# T4F81_FPGA.net
KiCad netlist of a schematic drawn in Altium Designer
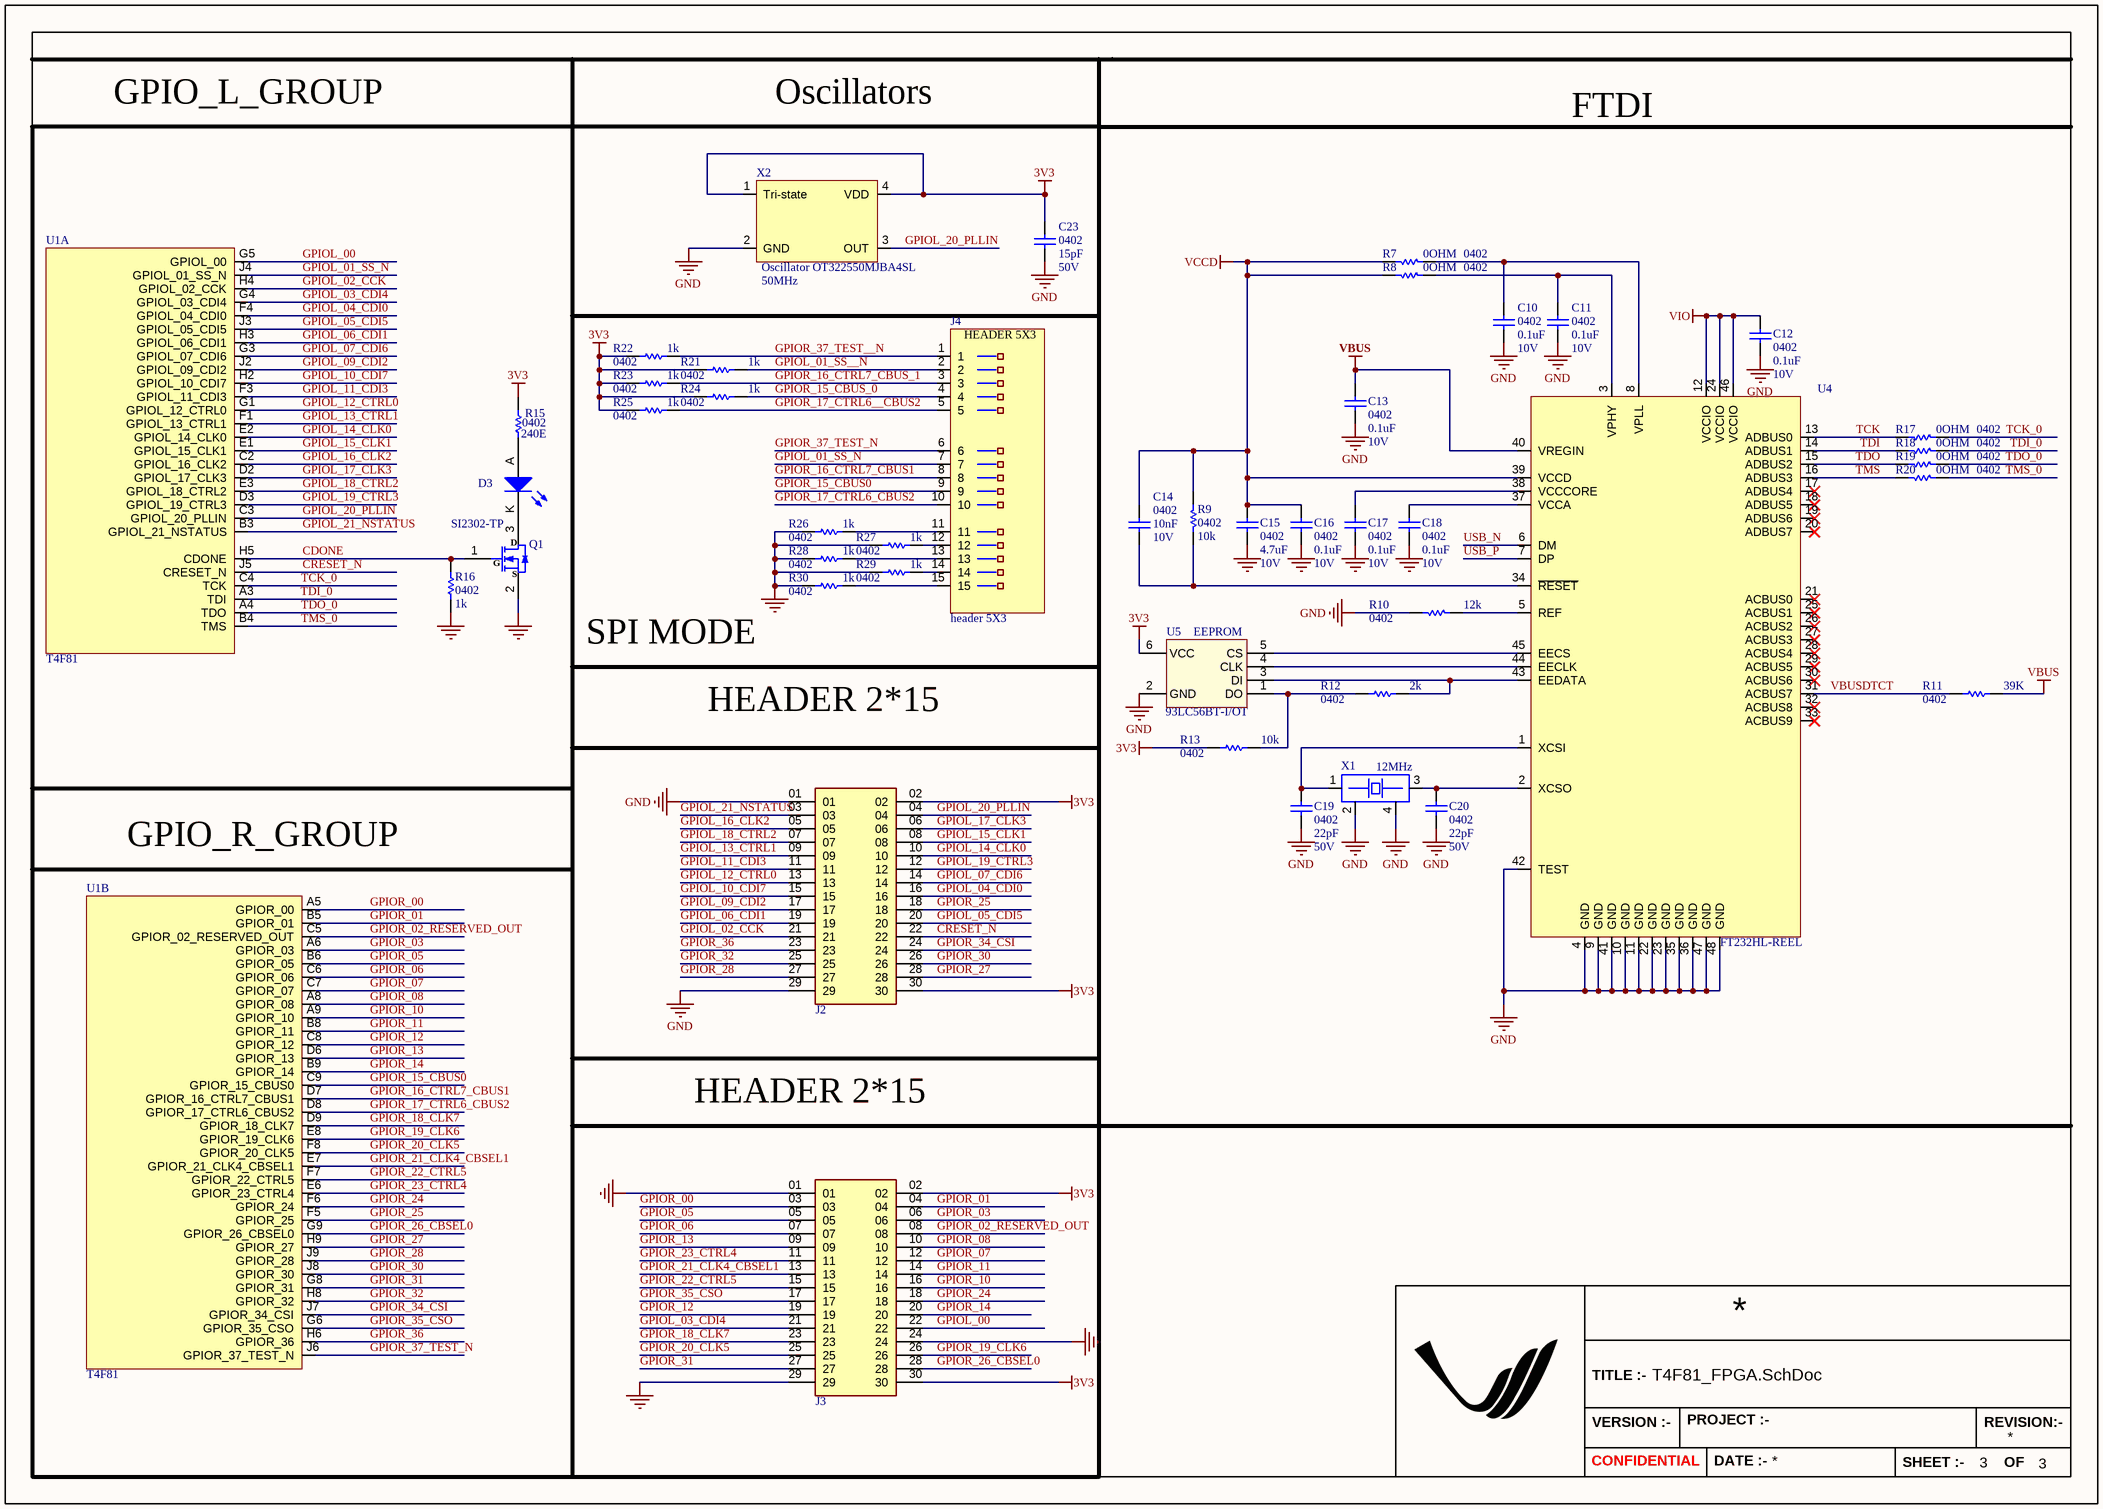
[diagram p0: T4F81_FPGA.SchDoc]

(export (version "E")
  (design (tool "Eeschema 10.0.6"))
  (components
    (comp (ref "C10")
      (value "0.1uF")
      (footprint "CAPC0402")
      (description "Ceramic Capacitor, 0.1uF, 0402,10V")
      (fields (field (name "CASE/PACKAGE") "0402") (field (name "VOLTAGE") "10V"))
      (libsource (lib "Pd's Sch Lib") (part "Capacitor"))
    )
    (comp (ref "C11")
      (value "0.1uF")
      (footprint "CAPC0402")
      (description "Ceramic Capacitor, 0.1uF, 0402,10V")
      (fields (field (name "CASE/PACKAGE") "0402") (field (name "VOLTAGE") "10V"))
      (libsource (lib "Pd's Sch Lib") (part "Capacitor"))
    )
    (comp (ref "C12")
      (value "0.1uF")
      (footprint "CAPC0402")
      (description "Ceramic Capacitor, 0.1uF, 0402,10V")
      (fields (field (name "CASE/PACKAGE") "0402") (field (name "VOLTAGE") "10V"))
      (libsource (lib "Pd's Sch Lib") (part "Capacitor"))
    )
    (comp (ref "C13")
      (value "0.1uF")
      (footprint "CAPC0402")
      (description "Ceramic Capacitor, 0.1uF, 0402,10V")
      (fields (field (name "CASE/PACKAGE") "0402") (field (name "VOLTAGE") "10V"))
      (libsource (lib "Pd's Sch Lib") (part "Capacitor"))
    )
    (comp (ref "C14")
      (value "10nF")
      (footprint "CAPC0402")
      (description "Ceramic Capacitor, 10nF, 0402,10V")
      (fields (field (name "CASE/PACKAGE") "0402") (field (name "VOLTAGE") "10V"))
      (libsource (lib "Pd's Sch Lib") (part "Capacitor"))
    )
    (comp (ref "C15")
      (value "4.7uF")
      (footprint "CAPC0402")
      (description "Ceramic Capacitor, 4.7uF, 0402,10V")
      (fields (field (name "CASE/PACKAGE") "0402") (field (name "VOLTAGE") "10V"))
      (libsource (lib "Pd's Sch Lib") (part "Capacitor"))
    )
    (comp (ref "C16")
      (value "0.1uF")
      (footprint "CAPC0402")
      (description "Ceramic Capacitor, 0.1UF, 0402,10V")
      (fields (field (name "CASE/PACKAGE") "0402") (field (name "VOLTAGE") "10V"))
      (libsource (lib "Pd's Sch Lib") (part "Capacitor"))
    )
    (comp (ref "C17")
      (value "0.1uF")
      (footprint "CAPC0402")
      (description "Ceramic Capacitor, 0.1UF, 0402,10V")
      (fields (field (name "CASE/PACKAGE") "0402") (field (name "VOLTAGE") "10V"))
      (libsource (lib "Pd's Sch Lib") (part "Capacitor"))
    )
    (comp (ref "C18")
      (value "0.1uF")
      (footprint "CAPC0402")
      (description "Ceramic Capacitor, 0.1UF, 0402,10V")
      (fields (field (name "CASE/PACKAGE") "0402") (field (name "VOLTAGE") "10V"))
      (libsource (lib "Pd's Sch Lib") (part "Capacitor"))
    )
    (comp (ref "C19")
      (value "22pF")
      (footprint "CAPC0402")
      (description "Ceramic Capacitor, 22pF, 0402,50V")
      (fields (field (name "CASE/PACKAGE") "0402") (field (name "VOLTAGE") "50V"))
      (libsource (lib "Pd's Sch Lib") (part "Capacitor"))
    )
    (comp (ref "C20")
      (value "22pF")
      (footprint "CAPC0402")
      (description "Ceramic Capacitor, 22pF, 0402,50V")
      (fields (field (name "CASE/PACKAGE") "0402") (field (name "VOLTAGE") "50V"))
      (libsource (lib "Pd's Sch Lib") (part "Capacitor"))
    )
    (comp (ref "C23")
      (value "15pF")
      (footprint "CAPC0402")
      (description "Ceramic Capacitor, 15pF, 0402,50V")
      (fields (field (name "CASE/PACKAGE") "0402") (field (name "VOLTAGE") "50V"))
      (libsource (lib "Pd's Sch Lib") (part "Capacitor"))
    )
    (comp (ref "D3")
      (value "~")
      (footprint "led_0603")
      (description "GREEN LED, 0603")
      (fields (field (name "MANUFACTURER PART NUMBER") "GREEN"))
      (libsource (lib "CUSTOM TNY290PG") (part "LED1"))
    )
    (comp (ref "J2")
      (value "Header 15X2 2.54mm")
      (footprint "Header_15X2_2.54")
      (description "Connector Header position")
      (fields (field (name "MANUFACTURER PART NUMBER") "Th P2.54MM"))
      (libsource (lib "CUSTOM SCH") (part "Header 15X2 2.54mm"))
    )
    (comp (ref "J3")
      (value "Header 15X2 2.54mm")
      (footprint "Header_15X2_2.54")
      (description "Connector Header position")
      (fields (field (name "MANUFACTURER PART NUMBER") "Th P2.54MM"))
      (libsource (lib "CUSTOM SCH") (part "Header 15X2 2.54mm"))
    )
    (comp (ref "J4")
      (value "header 5X3")
      (footprint "HEADER_5X3_2.54 - duplicate")
      (description "HEADER 5X3 2.54MM")
      (libsource (lib "CUSTOM SCH") (part "header 5X3"))
    )
    (comp (ref "Q1")
      (value "~")
      (footprint "SOT23-3")
      (description "N-Channel 20V 3A 1.25W (Ta) Surface Mount SOT-23")
      (fields (field (name "MANUFACTURER PART NUMBER") "SI2302-TP"))
      (libsource (lib "SchLib_SPEEDSTER7T_AC7T1500") (part "MOSFET Si2302CDS"))
    )
    (comp (ref "R7")
      (value "0OHM")
      (footprint "resc0402")
      (description "Thick Film Resistor -  0ohm, 1%, 0402")
      (fields
        (field (name "MANUFACTURER PART NUMBER") "RC0402FR-070RL")
        (field (name "CASE/PACKAGE") "0402")
        (field (name "Comment") "Res1")
      )
      (libsource (lib "Miscellaneous Devices") (part "Res1"))
    )
    (comp (ref "R8")
      (value "0OHM")
      (footprint "resc0402")
      (description "Thick Film Resistor -  0ohm, 1%, 0402")
      (fields (field (name "CASE/PACKAGE") "0402") (field (name "Comment") "Res1"))
      (libsource (lib "Miscellaneous Devices") (part "Res1"))
    )
    (comp (ref "R9")
      (value "10k")
      (footprint "RESC0402")
      (description "Thick Film Resistor -  10Kohm, 1%, 0402")
      (fields (field (name "CASE/PACKAGE") "0402") (field (name "Comment") "Res1"))
      (libsource (lib "Miscellaneous Devices") (part "Res1"))
    )
    (comp (ref "R10")
      (value "12k")
      (footprint "resc0402")
      (description "Thick Film Resistor -  12Kohm, 1%, 0402")
      (fields (field (name "CASE/PACKAGE") "0402") (field (name "Comment") "Res1"))
      (libsource (lib "Miscellaneous Devices") (part "Res1"))
    )
    (comp (ref "R11")
      (value "39K")
      (footprint "CAPC0402")
      (description "Thick Film Resistor -  39Kohm, 1%, 0402")
      (fields (field (name "CASE/PACKAGE") "0402") (field (name "Comment") "Res1"))
      (libsource (lib "Miscellaneous Devices") (part "Res1"))
    )
    (comp (ref "R12")
      (value "2k")
      (footprint "resc0402")
      (description "Thick Film Resistor -  2Kohm, 1%, 0402")
      (fields (field (name "CASE/PACKAGE") "0402") (field (name "Comment") "Res1"))
      (libsource (lib "Miscellaneous Devices") (part "Res1"))
    )
    (comp (ref "R13")
      (value "10k")
      (footprint "resc0402")
      (description "Thick Film Resistor -  10Kohm, 1%, 0402")
      (fields (field (name "CASE/PACKAGE") "0402") (field (name "Comment") "Res1"))
      (libsource (lib "Miscellaneous Devices") (part "Res1"))
    )
    (comp (ref "R15")
      (value "240E")
      (footprint "RESC0402")
      (description "Thick Film Resistor -  240ohm, 1%, 0402")
      (fields (field (name "CASE/PACKAGE") "0402"))
      (libsource (lib "CUSTOM TNY290PG") (part "Res"))
    )
    (comp (ref "R16")
      (value "1k")
      (footprint "RESC0402")
      (description "Thick Film Resistor -  1Kohm, 1%, 0402")
      (fields (field (name "CASE/PACKAGE") "0402"))
      (libsource (lib "CUSTOM TNY290PG") (part "Res"))
    )
    (comp (ref "R17")
      (value "0OHM")
      (footprint "resc0402")
      (description "Thick Film Resistor -  0ohm, 1%, 0402")
      (fields
        (field (name "MANUFACTURER PART NUMBER") "RC0402FR-070RL")
        (field (name "CASE/PACKAGE") "0402")
        (field (name "Comment") "Res1")
      )
      (libsource (lib "Miscellaneous Devices") (part "Res1"))
    )
    (comp (ref "R18")
      (value "0OHM")
      (footprint "resc0402")
      (description "Thick Film Resistor -  0ohm, 1%, 0402")
      (fields
        (field (name "MANUFACTURER PART NUMBER") "RC0402FR-070RL")
        (field (name "CASE/PACKAGE") "0402")
        (field (name "Comment") "Res1")
      )
      (libsource (lib "Miscellaneous Devices") (part "Res1"))
    )
    (comp (ref "R19")
      (value "0OHM")
      (footprint "resc0402")
      (description "Thick Film Resistor -  0ohm, 1%, 0402")
      (fields
        (field (name "MANUFACTURER PART NUMBER") "RC0402FR-070RL")
        (field (name "CASE/PACKAGE") "0402")
        (field (name "Comment") "Res1")
      )
      (libsource (lib "Miscellaneous Devices") (part "Res1"))
    )
    (comp (ref "R20")
      (value "0OHM")
      (footprint "resc0402")
      (description "Thick Film Resistor -  0ohm, 1%, 0402")
      (fields
        (field (name "MANUFACTURER PART NUMBER") "RC0402FR-070RL")
        (field (name "CASE/PACKAGE") "0402")
        (field (name "Comment") "Res1")
      )
      (libsource (lib "Miscellaneous Devices") (part "Res1"))
    )
    (comp (ref "R21")
      (value "1k")
      (footprint "resc0402")
      (description "Thick Film Resistor -  1Kohm, 1%, 0402")
      (fields (field (name "CASE/PACKAGE") "0402") (field (name "Comment") "Res1"))
      (libsource (lib "Miscellaneous Devices") (part "Res1"))
    )
    (comp (ref "R22")
      (value "1k")
      (footprint "resc0402")
      (description "Thick Film Resistor -  1Kohm, 1%, 0402")
      (fields (field (name "CASE/PACKAGE") "0402") (field (name "Comment") "Res1"))
      (libsource (lib "Miscellaneous Devices") (part "Res1"))
    )
    (comp (ref "R23")
      (value "1k")
      (footprint "resc0402")
      (description "Thick Film Resistor -  1Kohm, 1%, 0402")
      (fields (field (name "CASE/PACKAGE") "0402") (field (name "Comment") "Res1"))
      (libsource (lib "Miscellaneous Devices") (part "Res1"))
    )
    (comp (ref "R24")
      (value "1k")
      (footprint "resc0402")
      (description "Thick Film Resistor -  1Kohm, 1%, 0402")
      (fields (field (name "CASE/PACKAGE") "0402") (field (name "Comment") "Res1"))
      (libsource (lib "Miscellaneous Devices") (part "Res1"))
    )
    (comp (ref "R25")
      (value "1k")
      (footprint "resc0402")
      (description "Thick Film Resistor -  1Kohm, 1%, 0402")
      (fields (field (name "CASE/PACKAGE") "0402") (field (name "Comment") "Res1"))
      (libsource (lib "Miscellaneous Devices") (part "Res1"))
    )
    (comp (ref "R26")
      (value "1k")
      (footprint "resc0402")
      (description "Thick Film Resistor -  1Kohm, 1%, 0402")
      (fields (field (name "CASE/PACKAGE") "0402") (field (name "Comment") "Res1"))
      (libsource (lib "Miscellaneous Devices") (part "Res1"))
    )
    (comp (ref "R27")
      (value "1k")
      (footprint "resc0402")
      (description "Thick Film Resistor -  1Kohm, 1%, 0402")
      (fields (field (name "CASE/PACKAGE") "0402") (field (name "Comment") "Res1"))
      (libsource (lib "Miscellaneous Devices") (part "Res1"))
    )
    (comp (ref "R28")
      (value "1k")
      (footprint "resc0402")
      (description "Thick Film Resistor -  1Kohm, 1%, 0402")
      (fields (field (name "CASE/PACKAGE") "0402") (field (name "Comment") "Res1"))
      (libsource (lib "Miscellaneous Devices") (part "Res1"))
    )
    (comp (ref "R29")
      (value "1k")
      (footprint "resc0402")
      (description "Thick Film Resistor -  1Kohm, 1%, 0402")
      (fields (field (name "CASE/PACKAGE") "0402") (field (name "Comment") "Res1"))
      (libsource (lib "Miscellaneous Devices") (part "Res1"))
    )
    (comp (ref "R30")
      (value "1k")
      (footprint "resc0402")
      (description "Thick Film Resistor -  1Kohm, 1%, 0402")
      (fields (field (name "CASE/PACKAGE") "0402") (field (name "Comment") "Res1"))
      (libsource (lib "Miscellaneous Devices") (part "Res1"))
    )
    (comp (ref "U1") (value "T4F81") (footprint "T4F81 fpga") (libsource (lib "CUSTOM SCH") (part "T4F81")))
    (comp (ref "U4")
      (value "FTDI")
      (footprint "LQFP-48")
      (fields (field (name "MANUFACTURER PART NUMBER") "FT232HL-REEL"))
      (libsource (lib "Pd's Sch Lib") (part "FT232HL"))
    )
    (comp (ref "U5")
      (value "93LC56BT-I/OT")
      (footprint "SOT23-6")
      (description "MICROCHIP - 93LC56BT-I/OT. - 2K, 128 X 16, SERIAL EE, IND ROHS COMPLIANT: YES")
      (fields (field (name "TYPE") "EEPROM") (field (name "MANUFACTURER PART NUMBER") "93LC56BT-I/OT"))
      (libsource (lib "CUSTOM TNY290PG") (part "93LC56BT-I/OT"))
    )
    (comp (ref "X1")
      (value "XC2426TR-ND")
      (footprint "Crystal_3225")
      (description "CRYSTAL 12.0000MHZ 10PF SMD")
      (fields
        (field (name "MANUFACTURER PART NUMBER") "ECS-120-10-33B-CKM-TR")
        (field (name "FREQUENCY") "12MHz")
      )
      (libsource (lib "Pd's Sch Lib") (part "CRYSTAL_1_1"))
    )
    (comp (ref "X2")
      (value "Oscillator OT322550MJBA4SL")
      (footprint "Crystal_3225")
      (description "1.8V~3.3V -40℃~+85℃ ±10ppm 50MHz SMD3225-4P Oscillators ROHS (OT322550MJBA4SL) (C717684)")
      (fields (field (name "MANUFACTURER PART NUMBER") "OT322550MJBA4SL") (field (name "FREQUENCY") "50MHz"))
      (libsource (lib "CUSTOM SCH") (part "Oscillator OT322550MJBA4SL"))
    )
  )
  (nets
    (net (code "1") (name "/CDONE") (class "Default")
      (node (ref "Q1") (pin "1") (pinfunction "G_1") (pintype "passive"))
      (node (ref "R16") (pin "1") (pinfunction "1_1") (pintype "passive"))
      (node (ref "U1") (pin "H5") (pinfunction "CDONE_H5") (pintype "passive"))
    )
    (net (code "2") (name "/CRESET_N") (class "Default")
      (node (ref "J2") (pin "22") (pinfunction "22_22") (pintype "passive"))
      (node (ref "U1") (pin "J5") (pinfunction "CRESET_N_J5") (pintype "passive"))
    )
    (net (code "3") (name "/GPIOL_00") (class "Default")
      (node (ref "J3") (pin "22") (pinfunction "22_22") (pintype "passive"))
      (node (ref "U1") (pin "G5") (pinfunction "GPIOL_00_G5") (pintype "passive"))
    )
    (net (code "4") (name "/GPIOL_01_SS_N") (class "Default")
      (node (ref "J4") (pin "7") (pinfunction "7_7") (pintype "passive"))
      (node (ref "U1") (pin "J4") (pinfunction "GPIOL_01_SS_N_J4") (pintype "passive"))
    )
    (net (code "5") (name "/GPIOL_01_SS__N") (class "Default")
      (node (ref "J4") (pin "2") (pinfunction "2_2") (pintype "passive"))
      (node (ref "R21") (pin "1") (pinfunction "1_1") (pintype "passive"))
    )
    (net (code "6") (name "/GPIOL_02_CCK") (class "Default")
      (node (ref "J2") (pin "21") (pinfunction "21_21") (pintype "passive"))
      (node (ref "U1") (pin "H4") (pinfunction "GPIOL_02_CCK_H4") (pintype "passive"))
    )
    (net (code "7") (name "/GPIOL_03_CDI4") (class "Default")
      (node (ref "J3") (pin "21") (pinfunction "21_21") (pintype "passive"))
      (node (ref "U1") (pin "G4") (pinfunction "GPIOL_03_CDI4_G4") (pintype "passive"))
    )
    (net (code "8") (name "/GPIOL_04_CDI0") (class "Default")
      (node (ref "J2") (pin "16") (pinfunction "16_16") (pintype "passive"))
      (node (ref "U1") (pin "F4") (pinfunction "GPIOL_04_CDI0_F4") (pintype "passive"))
    )
    (net (code "9") (name "/GPIOL_05_CDI5") (class "Default")
      (node (ref "J2") (pin "20") (pinfunction "20_20") (pintype "passive"))
      (node (ref "U1") (pin "J3") (pinfunction "GPIOL_05_CDI5_J3") (pintype "passive"))
    )
    (net (code "10") (name "/GPIOL_06_CDI1") (class "Default")
      (node (ref "J2") (pin "19") (pinfunction "19_19") (pintype "passive"))
      (node (ref "U1") (pin "H3") (pinfunction "GPIOL_06_CDI1_H3") (pintype "passive"))
    )
    (net (code "11") (name "/GPIOL_07_CDI6") (class "Default")
      (node (ref "J2") (pin "14") (pinfunction "14_14") (pintype "passive"))
      (node (ref "U1") (pin "G3") (pinfunction "GPIOL_07_CDI6_G3") (pintype "passive"))
    )
    (net (code "12") (name "/GPIOL_09_CDI2") (class "Default")
      (node (ref "J2") (pin "17") (pinfunction "17_17") (pintype "passive"))
      (node (ref "U1") (pin "J2") (pinfunction "GPIOL_09_CDI2_J2") (pintype "passive"))
    )
    (net (code "13") (name "/GPIOL_10_CDI7") (class "Default")
      (node (ref "J2") (pin "15") (pinfunction "15_15") (pintype "passive"))
      (node (ref "U1") (pin "H2") (pinfunction "GPIOL_10_CDI7_H2") (pintype "passive"))
    )
    (net (code "14") (name "/GPIOL_11_CDI3") (class "Default")
      (node (ref "J2") (pin "11") (pinfunction "11_11") (pintype "passive"))
      (node (ref "U1") (pin "F3") (pinfunction "GPIOL_11_CDI3_F3") (pintype "passive"))
    )
    (net (code "15") (name "/GPIOL_12_CTRL0") (class "Default")
      (node (ref "J2") (pin "13") (pinfunction "13_13") (pintype "passive"))
      (node (ref "U1") (pin "G1") (pinfunction "GPIOL_12_CTRL0_G1") (pintype "passive"))
    )
    (net (code "16") (name "/GPIOL_13_CTRL1") (class "Default")
      (node (ref "J2") (pin "09") (pinfunction "09_09") (pintype "passive"))
      (node (ref "U1") (pin "F1") (pinfunction "GPIOL_13_CTRL1_F1") (pintype "passive"))
    )
    (net (code "17") (name "/GPIOL_14_CLK0") (class "Default")
      (node (ref "J2") (pin "10") (pinfunction "10_10") (pintype "passive"))
      (node (ref "U1") (pin "E2") (pinfunction "GPIOL_14_CLK0_E2") (pintype "passive"))
    )
    (net (code "18") (name "/GPIOL_15_CLK1") (class "Default")
      (node (ref "J2") (pin "08") (pinfunction "08_08") (pintype "passive"))
      (node (ref "U1") (pin "E1") (pinfunction "GPIOL_15_CLK1_E1") (pintype "passive"))
    )
    (net (code "19") (name "/GPIOL_16_CLK2") (class "Default")
      (node (ref "J2") (pin "05") (pinfunction "05_05") (pintype "passive"))
      (node (ref "U1") (pin "C2") (pinfunction "GPIOL_16_CLK2_C2") (pintype "passive"))
    )
    (net (code "20") (name "/GPIOL_17_CLK3") (class "Default")
      (node (ref "J2") (pin "06") (pinfunction "06_06") (pintype "passive"))
      (node (ref "U1") (pin "D2") (pinfunction "GPIOL_17_CLK3_D2") (pintype "passive"))
    )
    (net (code "21") (name "/GPIOL_18_CTRL2") (class "Default")
      (node (ref "J2") (pin "07") (pinfunction "07_07") (pintype "passive"))
      (node (ref "U1") (pin "E3") (pinfunction "GPIOL_18_CTRL2_E3") (pintype "passive"))
    )
    (net (code "22") (name "/GPIOL_19_CTRL3") (class "Default")
      (node (ref "J2") (pin "12") (pinfunction "12_12") (pintype "passive"))
      (node (ref "U1") (pin "D3") (pinfunction "GPIOL_19_CTRL3_D3") (pintype "passive"))
    )
    (net (code "23") (name "/GPIOL_20_PLLIN") (class "Default")
      (node (ref "J2") (pin "04") (pinfunction "04_04") (pintype "passive"))
      (node (ref "U1") (pin "C3") (pinfunction "GPIOL_20_PLLIN_C3") (pintype "passive"))
      (node (ref "X2") (pin "3") (pinfunction "OUT_3") (pintype "passive"))
    )
    (net (code "24") (name "/GPIOL_21_NSTATUS") (class "Default")
      (node (ref "J2") (pin "03") (pinfunction "03_03") (pintype "passive"))
      (node (ref "U1") (pin "B3") (pinfunction "GPIOL_21_NSTATUS_B3") (pintype "passive"))
    )
    (net (code "25") (name "/GPIOR_00") (class "Default")
      (node (ref "J3") (pin "03") (pinfunction "03_03") (pintype "passive"))
      (node (ref "U1") (pin "A5") (pinfunction "GPIOR_00_A5") (pintype "passive"))
    )
    (net (code "26") (name "/GPIOR_01") (class "Default")
      (node (ref "J3") (pin "04") (pinfunction "04_04") (pintype "passive"))
      (node (ref "U1") (pin "B5") (pinfunction "GPIOR_01_B5") (pintype "passive"))
    )
    (net (code "27") (name "/GPIOR_02_RESERVED_OUT") (class "Default")
      (node (ref "J3") (pin "08") (pinfunction "08_08") (pintype "passive"))
      (node (ref "U1") (pin "C5") (pinfunction "GPIOR_02_RESERVED_OUT_C5") (pintype "passive"))
    )
    (net (code "28") (name "/GPIOR_03") (class "Default")
      (node (ref "J3") (pin "06") (pinfunction "06_06") (pintype "passive"))
      (node (ref "U1") (pin "A6") (pinfunction "GPIOR_03_A6") (pintype "passive"))
    )
    (net (code "29") (name "/GPIOR_05") (class "Default")
      (node (ref "J3") (pin "05") (pinfunction "05_05") (pintype "passive"))
      (node (ref "U1") (pin "B6") (pinfunction "GPIOR_05_B6") (pintype "passive"))
    )
    (net (code "30") (name "/GPIOR_06") (class "Default")
      (node (ref "J3") (pin "07") (pinfunction "07_07") (pintype "passive"))
      (node (ref "U1") (pin "C6") (pinfunction "GPIOR_06_C6") (pintype "passive"))
    )
    (net (code "31") (name "/GPIOR_07") (class "Default")
      (node (ref "J3") (pin "12") (pinfunction "12_12") (pintype "passive"))
      (node (ref "U1") (pin "C7") (pinfunction "GPIOR_07_C7") (pintype "passive"))
    )
    (net (code "32") (name "/GPIOR_08") (class "Default")
      (node (ref "J3") (pin "10") (pinfunction "10_10") (pintype "passive"))
      (node (ref "U1") (pin "A8") (pinfunction "GPIOR_08_A8") (pintype "passive"))
    )
    (net (code "33") (name "/GPIOR_10") (class "Default")
      (node (ref "J3") (pin "16") (pinfunction "16_16") (pintype "passive"))
      (node (ref "U1") (pin "A9") (pinfunction "GPIOR_10_A9") (pintype "passive"))
    )
    (net (code "34") (name "/GPIOR_11") (class "Default")
      (node (ref "J3") (pin "14") (pinfunction "14_14") (pintype "passive"))
      (node (ref "U1") (pin "B8") (pinfunction "GPIOR_11_B8") (pintype "passive"))
    )
    (net (code "35") (name "/GPIOR_12") (class "Default")
      (node (ref "J3") (pin "19") (pinfunction "19_19") (pintype "passive"))
      (node (ref "U1") (pin "C8") (pinfunction "GPIOR_12_C8") (pintype "passive"))
    )
    (net (code "36") (name "/GPIOR_13") (class "Default")
      (node (ref "J3") (pin "09") (pinfunction "09_09") (pintype "passive"))
      (node (ref "U1") (pin "D6") (pinfunction "GPIOR_13_D6") (pintype "passive"))
    )
    (net (code "37") (name "/GPIOR_14") (class "Default")
      (node (ref "J3") (pin "20") (pinfunction "20_20") (pintype "passive"))
      (node (ref "U1") (pin "B9") (pinfunction "GPIOR_14_B9") (pintype "passive"))
    )
    (net (code "38") (name "/GPIOR_15_CBUS0") (class "Default")
      (node (ref "J4") (pin "9") (pinfunction "9_9") (pintype "passive"))
      (node (ref "U1") (pin "C9") (pinfunction "GPIOR_15_CBUS0_C9") (pintype "passive"))
    )
    (net (code "39") (name "/GPIOR_15_CBUS_0") (class "Default")
      (node (ref "J4") (pin "4") (pinfunction "4_4") (pintype "passive"))
      (node (ref "R24") (pin "1") (pinfunction "1_1") (pintype "passive"))
    )
    (net (code "40") (name "/GPIOR_16_CTRL7_CBUS1") (class "Default")
      (node (ref "J4") (pin "8") (pinfunction "8_8") (pintype "passive"))
      (node (ref "U1") (pin "D7") (pinfunction "GPIOR_16_CTRL7_CBUS1_D7") (pintype "passive"))
    )
    (net (code "41") (name "/GPIOR_16_CTRL7_CBUS_1") (class "Default")
      (node (ref "J4") (pin "3") (pinfunction "3_3") (pintype "passive"))
      (node (ref "R23") (pin "1") (pinfunction "1_1") (pintype "passive"))
    )
    (net (code "42") (name "/GPIOR_17_CTRL6_CBUS2") (class "Default")
      (node (ref "J4") (pin "10") (pinfunction "10_10") (pintype "passive"))
      (node (ref "U1") (pin "D8") (pinfunction "GPIOR_17_CTRL6_CBUS2_D8") (pintype "passive"))
    )
    (net (code "43") (name "/GPIOR_17_CTRL6__CBUS2") (class "Default")
      (node (ref "J4") (pin "5") (pinfunction "5_5") (pintype "passive"))
      (node (ref "R25") (pin "1") (pinfunction "1_1") (pintype "passive"))
    )
    (net (code "44") (name "/GPIOR_18_CLK7") (class "Default")
      (node (ref "J3") (pin "23") (pinfunction "23_23") (pintype "passive"))
      (node (ref "U1") (pin "D9") (pinfunction "GPIOR_18_CLK7_D9") (pintype "passive"))
    )
    (net (code "45") (name "/GPIOR_19_CLK6") (class "Default")
      (node (ref "J3") (pin "26") (pinfunction "26_26") (pintype "passive"))
      (node (ref "U1") (pin "E8") (pinfunction "GPIOR_19_CLK6_E8") (pintype "passive"))
    )
    (net (code "46") (name "/GPIOR_20_CLK5") (class "Default")
      (node (ref "J3") (pin "25") (pinfunction "25_25") (pintype "passive"))
      (node (ref "U1") (pin "F8") (pinfunction "GPIOR_20_CLK5_F8") (pintype "passive"))
    )
    (net (code "47") (name "/GPIOR_21_CLK4_CBSEL1") (class "Default")
      (node (ref "J3") (pin "13") (pinfunction "13_13") (pintype "passive"))
      (node (ref "U1") (pin "E7") (pinfunction "GPIOR_21_CLK4_CBSEL1_E7") (pintype "passive"))
    )
    (net (code "48") (name "/GPIOR_22_CTRL5") (class "Default")
      (node (ref "J3") (pin "15") (pinfunction "15_15") (pintype "passive"))
      (node (ref "U1") (pin "F7") (pinfunction "GPIOR_22_CTRL5_F7") (pintype "passive"))
    )
    (net (code "49") (name "/GPIOR_23_CTRL4") (class "Default")
      (node (ref "J3") (pin "11") (pinfunction "11_11") (pintype "passive"))
      (node (ref "U1") (pin "E6") (pinfunction "GPIOR_23_CTRL4_E6") (pintype "passive"))
    )
    (net (code "50") (name "/GPIOR_24") (class "Default")
      (node (ref "J3") (pin "18") (pinfunction "18_18") (pintype "passive"))
      (node (ref "U1") (pin "F6") (pinfunction "GPIOR_24_F6") (pintype "passive"))
    )
    (net (code "51") (name "/GPIOR_25") (class "Default")
      (node (ref "J2") (pin "18") (pinfunction "18_18") (pintype "passive"))
      (node (ref "U1") (pin "F5") (pinfunction "GPIOR_25_F5") (pintype "passive"))
    )
    (net (code "52") (name "/GPIOR_26_CBSEL0") (class "Default")
      (node (ref "J3") (pin "28") (pinfunction "28_28") (pintype "passive"))
      (node (ref "U1") (pin "G9") (pinfunction "GPIOR_26_CBSEL0_G9") (pintype "passive"))
    )
    (net (code "53") (name "/GPIOR_27") (class "Default")
      (node (ref "J2") (pin "28") (pinfunction "28_28") (pintype "passive"))
      (node (ref "U1") (pin "H9") (pinfunction "GPIOR_27_H9") (pintype "passive"))
    )
    (net (code "54") (name "/GPIOR_28") (class "Default")
      (node (ref "J2") (pin "27") (pinfunction "27_27") (pintype "passive"))
      (node (ref "U1") (pin "J9") (pinfunction "GPIOR_28_J9") (pintype "passive"))
    )
    (net (code "55") (name "/GPIOR_30") (class "Default")
      (node (ref "J2") (pin "26") (pinfunction "26_26") (pintype "passive"))
      (node (ref "U1") (pin "J8") (pinfunction "GPIOR_30_J8") (pintype "passive"))
    )
    (net (code "56") (name "/GPIOR_31") (class "Default")
      (node (ref "J3") (pin "27") (pinfunction "27_27") (pintype "passive"))
      (node (ref "U1") (pin "G8") (pinfunction "GPIOR_31_G8") (pintype "passive"))
    )
    (net (code "57") (name "/GPIOR_32") (class "Default")
      (node (ref "J2") (pin "25") (pinfunction "25_25") (pintype "passive"))
      (node (ref "U1") (pin "H8") (pinfunction "GPIOR_32_H8") (pintype "passive"))
    )
    (net (code "58") (name "/GPIOR_34_CSI") (class "Default")
      (node (ref "J2") (pin "24") (pinfunction "24_24") (pintype "passive"))
      (node (ref "U1") (pin "J7") (pinfunction "GPIOR_34_CSI_J7") (pintype "passive"))
    )
    (net (code "59") (name "/GPIOR_35_CSO") (class "Default")
      (node (ref "J3") (pin "17") (pinfunction "17_17") (pintype "passive"))
      (node (ref "U1") (pin "G6") (pinfunction "GPIOR_35_CSO_G6") (pintype "passive"))
    )
    (net (code "60") (name "/GPIOR_36") (class "Default")
      (node (ref "J2") (pin "23") (pinfunction "23_23") (pintype "passive"))
      (node (ref "U1") (pin "H6") (pinfunction "GPIOR_36_H6") (pintype "passive"))
    )
    (net (code "61") (name "/GPIOR_37_TEST_N") (class "Default")
      (node (ref "J4") (pin "6") (pinfunction "6_6") (pintype "passive"))
      (node (ref "U1") (pin "J6") (pinfunction "GPIOR_37_TEST_N_J6") (pintype "passive"))
    )
    (net (code "62") (name "/GPIOR_37_TEST__N") (class "Default")
      (node (ref "J4") (pin "1") (pinfunction "1_1") (pintype "passive"))
      (node (ref "R22") (pin "1") (pinfunction "1_1") (pintype "passive"))
    )
    (net (code "63") (name "/TCK") (class "Default")
      (node (ref "R17") (pin "2") (pinfunction "2_2") (pintype "passive"))
      (node (ref "U4") (pin "13") (pinfunction "ADBUS0_13") (pintype "passive"))
    )
    (net (code "64") (name "/TCK_0") (class "Default")
      (node (ref "R17") (pin "1") (pinfunction "1_1") (pintype "passive"))
      (node (ref "U1") (pin "C4") (pinfunction "TCK_C4") (pintype "passive"))
    )
    (net (code "65") (name "/TDI") (class "Default")
      (node (ref "R18") (pin "2") (pinfunction "2_2") (pintype "passive"))
      (node (ref "U4") (pin "14") (pinfunction "ADBUS1_14") (pintype "passive"))
    )
    (net (code "66") (name "/TDI_0") (class "Default")
      (node (ref "R18") (pin "1") (pinfunction "1_1") (pintype "passive"))
      (node (ref "U1") (pin "A3") (pinfunction "TDI_A3") (pintype "passive"))
    )
    (net (code "67") (name "/TDO") (class "Default")
      (node (ref "R19") (pin "2") (pinfunction "2_2") (pintype "passive"))
      (node (ref "U4") (pin "15") (pinfunction "ADBUS2_15") (pintype "passive"))
    )
    (net (code "68") (name "/TDO_0") (class "Default")
      (node (ref "R19") (pin "1") (pinfunction "1_1") (pintype "passive"))
      (node (ref "U1") (pin "A4") (pinfunction "TDO_A4") (pintype "passive"))
    )
    (net (code "69") (name "/TMS") (class "Default")
      (node (ref "R20") (pin "2") (pinfunction "2_2") (pintype "passive"))
      (node (ref "U4") (pin "16") (pinfunction "ADBUS3_16") (pintype "passive"))
    )
    (net (code "70") (name "/TMS_0") (class "Default")
      (node (ref "R20") (pin "1") (pinfunction "1_1") (pintype "passive"))
      (node (ref "U1") (pin "B4") (pinfunction "TMS_B4") (pintype "passive"))
    )
    (net (code "71") (name "/USB_N") (class "Default")
      (node (ref "U4") (pin "6") (pinfunction "DM_6") (pintype "passive"))
    )
    (net (code "72") (name "/USB_P") (class "Default")
      (node (ref "U4") (pin "7") (pinfunction "DP_7") (pintype "passive"))
    )
    (net (code "73") (name "/VBUSDTCT") (class "Default")
      (node (ref "R11") (pin "2") (pinfunction "2_2") (pintype "passive"))
      (node (ref "U4") (pin "31") (pinfunction "ACBUS7_31") (pintype "passive"))
    )
    (net (code "74") (name "3V3") (class "Default")
      (node (ref "C23") (pin "2") (pinfunction "2_2") (pintype "passive"))
      (node (ref "J2") (pin "02") (pinfunction "02_02") (pintype "passive"))
      (node (ref "J2") (pin "30") (pinfunction "30_30") (pintype "passive"))
      (node (ref "J3") (pin "02") (pinfunction "02_02") (pintype "passive"))
      (node (ref "J3") (pin "30") (pinfunction "30_30") (pintype "passive"))
      (node (ref "R13") (pin "1") (pinfunction "1_1") (pintype "passive"))
      (node (ref "R15") (pin "2") (pinfunction "2_2") (pintype "passive"))
      (node (ref "R21") (pin "2") (pinfunction "2_2") (pintype "passive"))
      (node (ref "R22") (pin "2") (pinfunction "2_2") (pintype "passive"))
      (node (ref "R23") (pin "2") (pinfunction "2_2") (pintype "passive"))
      (node (ref "R24") (pin "2") (pinfunction "2_2") (pintype "passive"))
      (node (ref "R25") (pin "2") (pinfunction "2_2") (pintype "passive"))
      (node (ref "U5") (pin "6") (pinfunction "VCC_6") (pintype "passive"))
      (node (ref "X2") (pin "1") (pinfunction "Tri-state_1") (pintype "passive"))
      (node (ref "X2") (pin "4") (pinfunction "VDD_4") (pintype "passive"))
    )
    (net (code "75") (name "GND") (class "Default")
      (node (ref "C10") (pin "1") (pinfunction "1_1") (pintype "passive"))
      (node (ref "C11") (pin "1") (pinfunction "1_1") (pintype "passive"))
      (node (ref "C12") (pin "1") (pinfunction "1_1") (pintype "passive"))
      (node (ref "C13") (pin "1") (pinfunction "1_1") (pintype "passive"))
      (node (ref "C15") (pin "1") (pinfunction "1_1") (pintype "passive"))
      (node (ref "C16") (pin "1") (pinfunction "1_1") (pintype "passive"))
      (node (ref "C17") (pin "1") (pinfunction "1_1") (pintype "passive"))
      (node (ref "C18") (pin "1") (pinfunction "1_1") (pintype "passive"))
      (node (ref "C19") (pin "1") (pinfunction "1_1") (pintype "passive"))
      (node (ref "C20") (pin "1") (pinfunction "1_1") (pintype "passive"))
      (node (ref "C23") (pin "1") (pinfunction "1_1") (pintype "passive"))
      (node (ref "J2") (pin "01") (pinfunction "01_01") (pintype "passive"))
      (node (ref "J2") (pin "29") (pinfunction "29_29") (pintype "passive"))
      (node (ref "J3") (pin "01") (pinfunction "01_01") (pintype "passive"))
      (node (ref "J3") (pin "24") (pinfunction "24_24") (pintype "passive"))
      (node (ref "J3") (pin "29") (pinfunction "29_29") (pintype "passive"))
      (node (ref "Q1") (pin "2") (pinfunction "S_2") (pintype "passive"))
      (node (ref "R10") (pin "1") (pinfunction "1_1") (pintype "passive"))
      (node (ref "R16") (pin "2") (pinfunction "2_2") (pintype "passive"))
      (node (ref "R26") (pin "2") (pinfunction "2_2") (pintype "passive"))
      (node (ref "R27") (pin "2") (pinfunction "2_2") (pintype "passive"))
      (node (ref "R28") (pin "2") (pinfunction "2_2") (pintype "passive"))
      (node (ref "R29") (pin "2") (pinfunction "2_2") (pintype "passive"))
      (node (ref "R30") (pin "2") (pinfunction "2_2") (pintype "passive"))
      (node (ref "U4") (pin "10") (pinfunction "GND_10") (pintype "passive"))
      (node (ref "U4") (pin "11") (pinfunction "GND_11") (pintype "passive"))
      (node (ref "U4") (pin "22") (pinfunction "GND_22") (pintype "passive"))
      (node (ref "U4") (pin "23") (pinfunction "GND_23") (pintype "passive"))
      (node (ref "U4") (pin "35") (pinfunction "GND_35") (pintype "passive"))
      (node (ref "U4") (pin "36") (pinfunction "GND_36") (pintype "passive"))
      (node (ref "U4") (pin "4") (pinfunction "GND_4") (pintype "passive"))
      (node (ref "U4") (pin "41") (pinfunction "GND_41") (pintype "passive"))
      (node (ref "U4") (pin "42") (pinfunction "TEST_42") (pintype "passive"))
      (node (ref "U4") (pin "47") (pinfunction "GND_47") (pintype "passive"))
      (node (ref "U4") (pin "48") (pinfunction "GND_48") (pintype "passive"))
      (node (ref "U4") (pin "9") (pinfunction "GND_9") (pintype "passive"))
      (node (ref "U5") (pin "2") (pinfunction "GND_2") (pintype "passive"))
      (node (ref "X1") (pin "2") (pinfunction "2_2") (pintype "passive"))
      (node (ref "X1") (pin "4") (pinfunction "4_4") (pintype "passive"))
      (node (ref "X2") (pin "2") (pinfunction "GND_2") (pintype "passive"))
    )
    (net (code "76") (name "Net-(D3-PadA)") (class "Default")
      (node (ref "D3") (pin "A") (pinfunction "A_A") (pintype "passive"))
      (node (ref "R15") (pin "1") (pinfunction "1_1") (pintype "passive"))
    )
    (net (code "77") (name "Net-(J4-Pad11)") (class "Default")
      (node (ref "J4") (pin "11") (pinfunction "11_11") (pintype "passive"))
      (node (ref "R26") (pin "1") (pinfunction "1_1") (pintype "passive"))
    )
    (net (code "78") (name "Net-(J4-Pad12)") (class "Default")
      (node (ref "J4") (pin "12") (pinfunction "12_12") (pintype "passive"))
      (node (ref "R27") (pin "1") (pinfunction "1_1") (pintype "passive"))
    )
    (net (code "79") (name "Net-(J4-Pad13)") (class "Default")
      (node (ref "J4") (pin "13") (pinfunction "13_13") (pintype "passive"))
      (node (ref "R28") (pin "1") (pinfunction "1_1") (pintype "passive"))
    )
    (net (code "80") (name "Net-(J4-Pad14)") (class "Default")
      (node (ref "J4") (pin "14") (pinfunction "14_14") (pintype "passive"))
      (node (ref "R29") (pin "1") (pinfunction "1_1") (pintype "passive"))
    )
    (net (code "81") (name "Net-(J4-Pad15)") (class "Default")
      (node (ref "J4") (pin "15") (pinfunction "15_15") (pintype "passive"))
      (node (ref "R30") (pin "1") (pinfunction "1_1") (pintype "passive"))
    )
    (net (code "82") (name "Net-(Q1-D)") (class "Default")
      (node (ref "D3") (pin "K") (pinfunction "K_K") (pintype "passive"))
      (node (ref "Q1") (pin "3") (pinfunction "D_3") (pintype "passive"))
    )
    (net (code "83") (name "Net-(U4-EECLK)") (class "Default")
      (node (ref "U4") (pin "44") (pinfunction "EECLK_44") (pintype "passive"))
      (node (ref "U5") (pin "4") (pinfunction "CLK_4") (pintype "passive"))
    )
    (net (code "84") (name "Net-(U4-EECS)") (class "Default")
      (node (ref "U4") (pin "45") (pinfunction "EECS_45") (pintype "passive"))
      (node (ref "U5") (pin "5") (pinfunction "CS_5") (pintype "passive"))
    )
    (net (code "85") (name "Net-(U4-EEDATA)") (class "Default")
      (node (ref "R12") (pin "2") (pinfunction "2_2") (pintype "passive"))
      (node (ref "U4") (pin "43") (pinfunction "EEDATA_43") (pintype "passive"))
      (node (ref "U5") (pin "3") (pinfunction "DI_3") (pintype "passive"))
    )
    (net (code "86") (name "Net-(U4-REF)") (class "Default")
      (node (ref "R10") (pin "2") (pinfunction "2_2") (pintype "passive"))
      (node (ref "U4") (pin "5") (pinfunction "REF_5") (pintype "passive"))
    )
    (net (code "87") (name "Net-(U4-VCCA)") (class "Default")
      (node (ref "C18") (pin "2") (pinfunction "2_2") (pintype "passive"))
      (node (ref "U4") (pin "37") (pinfunction "VCCA_37") (pintype "passive"))
    )
    (net (code "88") (name "Net-(U4-VCCCORE)") (class "Default")
      (node (ref "C17") (pin "2") (pinfunction "2_2") (pintype "passive"))
      (node (ref "U4") (pin "38") (pinfunction "VCCCORE_38") (pintype "passive"))
    )
    (net (code "89") (name "Net-(U4-VPHY)") (class "Default")
      (node (ref "C11") (pin "2") (pinfunction "2_2") (pintype "passive"))
      (node (ref "R8") (pin "1") (pinfunction "1_1") (pintype "passive"))
      (node (ref "U4") (pin "3") (pinfunction "VPHY_3") (pintype "passive"))
    )
    (net (code "90") (name "Net-(U4-VPLL)") (class "Default")
      (node (ref "C10") (pin "2") (pinfunction "2_2") (pintype "passive"))
      (node (ref "R7") (pin "1") (pinfunction "1_1") (pintype "passive"))
      (node (ref "U4") (pin "8") (pinfunction "VPLL_8") (pintype "passive"))
    )
    (net (code "91") (name "Net-(U4-XCSI)") (class "Default")
      (node (ref "C19") (pin "2") (pinfunction "2_2") (pintype "passive"))
      (node (ref "U4") (pin "1") (pinfunction "XCSI_1") (pintype "passive"))
      (node (ref "X1") (pin "1") (pinfunction "1_1") (pintype "passive"))
    )
    (net (code "92") (name "Net-(U4-XCSO)") (class "Default")
      (node (ref "C20") (pin "2") (pinfunction "2_2") (pintype "passive"))
      (node (ref "U4") (pin "2") (pinfunction "XCSO_2") (pintype "passive"))
      (node (ref "X1") (pin "3") (pinfunction "3_3") (pintype "passive"))
    )
    (net (code "93") (name "Net-(U4-~{RESET})") (class "Default")
      (node (ref "C14") (pin "1") (pinfunction "1_1") (pintype "passive"))
      (node (ref "R9") (pin "1") (pinfunction "1_1") (pintype "passive"))
      (node (ref "U4") (pin "34") (pinfunction "~{RESET}_34") (pintype "passive"))
    )
    (net (code "94") (name "Net-(U5-DO)") (class "Default")
      (node (ref "R12") (pin "1") (pinfunction "1_1") (pintype "passive"))
      (node (ref "R13") (pin "2") (pinfunction "2_2") (pintype "passive"))
      (node (ref "U5") (pin "1") (pinfunction "DO_1") (pintype "passive"))
    )
    (net (code "95") (name "VBUS") (class "Default")
      (node (ref "C13") (pin "2") (pinfunction "2_2") (pintype "passive"))
      (node (ref "R11") (pin "1") (pinfunction "1_1") (pintype "passive"))
      (node (ref "U4") (pin "40") (pinfunction "VREGIN_40") (pintype "passive"))
    )
    (net (code "96") (name "VCCD") (class "Default")
      (node (ref "C14") (pin "2") (pinfunction "2_2") (pintype "passive"))
      (node (ref "C15") (pin "2") (pinfunction "2_2") (pintype "passive"))
      (node (ref "C16") (pin "2") (pinfunction "2_2") (pintype "passive"))
      (node (ref "R7") (pin "2") (pinfunction "2_2") (pintype "passive"))
      (node (ref "R8") (pin "2") (pinfunction "2_2") (pintype "passive"))
      (node (ref "R9") (pin "2") (pinfunction "2_2") (pintype "passive"))
      (node (ref "U4") (pin "39") (pinfunction "VCCD_39") (pintype "passive"))
    )
    (net (code "97") (name "VIO") (class "Default")
      (node (ref "C12") (pin "2") (pinfunction "2_2") (pintype "passive"))
      (node (ref "U4") (pin "12") (pinfunction "VCCIO_12") (pintype "passive"))
      (node (ref "U4") (pin "24") (pinfunction "VCCIO_24") (pintype "passive"))
      (node (ref "U4") (pin "46") (pinfunction "VCCIO_46") (pintype "passive"))
    )
    (net (code "98") (name "unconnected-(U4-ACBUS0-Pad21)") (class "Default")
      (node (ref "U4") (pin "21") (pinfunction "ACBUS0_21") (pintype "passive+no_connect"))
    )
    (net (code "99") (name "unconnected-(U4-ACBUS1-Pad25)") (class "Default")
      (node (ref "U4") (pin "25") (pinfunction "ACBUS1_25") (pintype "passive+no_connect"))
    )
    (net (code "100") (name "unconnected-(U4-ACBUS2-Pad26)") (class "Default")
      (node (ref "U4") (pin "26") (pinfunction "ACBUS2_26") (pintype "passive+no_connect"))
    )
    (net (code "101") (name "unconnected-(U4-ACBUS3-Pad27)") (class "Default")
      (node (ref "U4") (pin "27") (pinfunction "ACBUS3_27") (pintype "passive+no_connect"))
    )
    (net (code "102") (name "unconnected-(U4-ACBUS4-Pad28)") (class "Default")
      (node (ref "U4") (pin "28") (pinfunction "ACBUS4_28") (pintype "passive+no_connect"))
    )
    (net (code "103") (name "unconnected-(U4-ACBUS5-Pad29)") (class "Default")
      (node (ref "U4") (pin "29") (pinfunction "ACBUS5_29") (pintype "passive+no_connect"))
    )
    (net (code "104") (name "unconnected-(U4-ACBUS6-Pad30)") (class "Default")
      (node (ref "U4") (pin "30") (pinfunction "ACBUS6_30") (pintype "passive+no_connect"))
    )
    (net (code "105") (name "unconnected-(U4-ACBUS8-Pad32)") (class "Default")
      (node (ref "U4") (pin "32") (pinfunction "ACBUS8_32") (pintype "passive+no_connect"))
    )
    (net (code "106") (name "unconnected-(U4-ACBUS9-Pad33)") (class "Default")
      (node (ref "U4") (pin "33") (pinfunction "ACBUS9_33") (pintype "passive+no_connect"))
    )
    (net (code "107") (name "unconnected-(U4-ADBUS4-Pad17)") (class "Default")
      (node (ref "U4") (pin "17") (pinfunction "ADBUS4_17") (pintype "passive+no_connect"))
    )
    (net (code "108") (name "unconnected-(U4-ADBUS5-Pad18)") (class "Default")
      (node (ref "U4") (pin "18") (pinfunction "ADBUS5_18") (pintype "passive+no_connect"))
    )
    (net (code "109") (name "unconnected-(U4-ADBUS6-Pad19)") (class "Default")
      (node (ref "U4") (pin "19") (pinfunction "ADBUS6_19") (pintype "passive+no_connect"))
    )
    (net (code "110") (name "unconnected-(U4-ADBUS7-Pad20)") (class "Default")
      (node (ref "U4") (pin "20") (pinfunction "ADBUS7_20") (pintype "passive+no_connect"))
    )
  )
)
